# VGA.net
KiCad netlist of a schematic drawn in Altium Designer
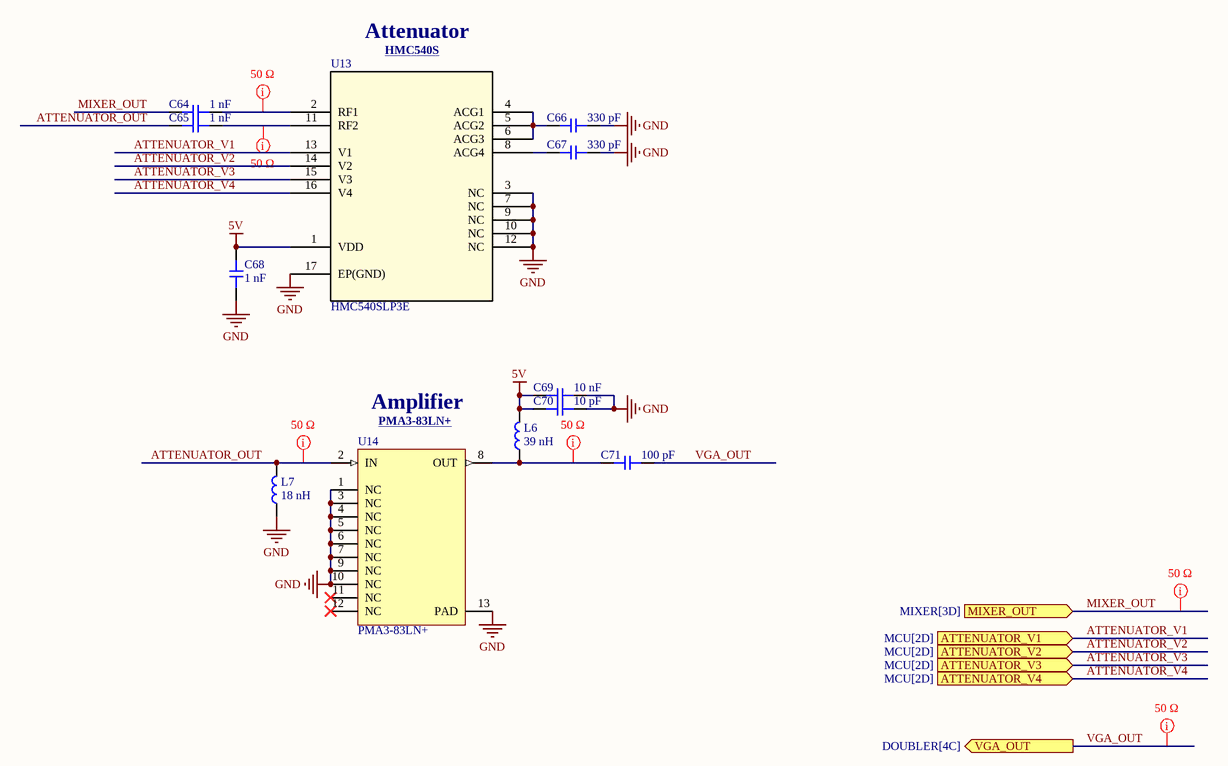
[diagram p0: VGA.SchDoc]

(export (version "E")
  (design (tool "Eeschema 10.0.6"))
  (components
    (comp (ref "C64")
      (value "1 nF")
      (footprint "CAP_0402")
      (description "50V 1nF X7R ±10% 0402 Multilayer Ceramic Capacitors MLCC - SMD/SMT ROHS")
      (fields
        (field (name "MANUFACTURER") "Yageo")
        (field (name "MANUFACTURER PART NUMBER") "CC0402KRX7R9BB102")
      )
      (libsource (lib "Titan") (part "CAP"))
    )
    (comp (ref "C65")
      (value "1 nF")
      (footprint "CAP_0402")
      (description "50V 1nF X7R ±10% 0402 Multilayer Ceramic Capacitors MLCC - SMD/SMT ROHS")
      (fields
        (field (name "MANUFACTURER") "Yageo")
        (field (name "MANUFACTURER PART NUMBER") "CC0402KRX7R9BB102")
      )
      (libsource (lib "Titan") (part "CAP"))
    )
    (comp (ref "C66")
      (value "330 pF")
      (footprint "CAP_0402")
      (description "50V 330pF C0G ±5% 0402 Multilayer Ceramic Capacitors MLCC - SMD/SMT ROHS")
      (fields
        (field (name "MANUFACTURER") "Murata Electronics")
        (field (name "MANUFACTURER PART NUMBER") "GRM1555C1H331JA01D")
      )
      (libsource (lib "Titan") (part "CAP"))
    )
    (comp (ref "C67")
      (value "330 pF")
      (footprint "CAP_0402")
      (description "50V 330pF C0G ±5% 0402 Multilayer Ceramic Capacitors MLCC - SMD/SMT ROHS")
      (fields
        (field (name "MANUFACTURER") "Murata Electronics")
        (field (name "MANUFACTURER PART NUMBER") "GRM1555C1H331JA01D")
      )
      (libsource (lib "Titan") (part "CAP"))
    )
    (comp (ref "C68")
      (value "1 nF")
      (footprint "CAP_0402")
      (description "50V 1nF X7R ±10% 0402 Multilayer Ceramic Capacitors MLCC - SMD/SMT ROHS")
      (fields
        (field (name "MANUFACTURER") "Yageo")
        (field (name "MANUFACTURER PART NUMBER") "CC0402KRX7R9BB102")
      )
      (libsource (lib "Titan") (part "CAP"))
    )
    (comp (ref "C69")
      (value "10 nF")
      (footprint "CAP_0402")
      (description "Multilayer Ceramic Capacitor, 0.01 uF, 25 V, ± 10%, X7R, 0402 [1005 Metric]")
      (fields
        (field (name "MANUFACTURER") "Murata Electronics")
        (field (name "MANUFACTURER PART NUMBER") "GRM155R71E103KA01D")
      )
      (libsource (lib "Titan") (part "CAP"))
    )
    (comp (ref "C70")
      (value "10 pF")
      (footprint "CAP_0402")
      (description "50V 10pF C0G ±1% 0402 Multilayer Ceramic Capacitors MLCC - SMD/SMT ROHS")
      (fields
        (field (name "MANUFACTURER") "Murata Electronics")
        (field (name "MANUFACTURER PART NUMBER") "GRM1555C1H100FA01D")
      )
      (libsource (lib "Titan") (part "CAP"))
    )
    (comp (ref "C71")
      (value "100 pF")
      (footprint "CAP_0402")
      (description "50V 100pF NP0 ±5% 0402 Multilayer Ceramic Capacitors MLCC - SMD/SMT ROHS")
      (fields
        (field (name "MANUFACTURER") "Yageo")
        (field (name "MANUFACTURER PART NUMBER") "CC0402JRNPO9BN101")
      )
      (libsource (lib "Titan") (part "CAP"))
    )
    (comp (ref "L6")
      (value "39 nH")
      (footprint "IND_0402")
      (description "Inductor RF Wirewound 0.039uH 5% 250MHz 25Q-Factor Ceramic 0.32A 0.55Ohm DCR 0402 T/R")
      (fields
        (field (name "MANUFACTURER") "Bourns Inc.")
        (field (name "MANUFACTURER PART NUMBER") "CW100505-39NJ")
      )
      (libsource (lib "Titan") (part "IND"))
    )
    (comp (ref "L7")
      (value "18 nH")
      (footprint "IND_0402")
      (description "Inductor RF Chip Multi-Layer 18nH 5% 100MHz 8Q-Factor Air 300mA 360mOhm DCR 0402 Paper T/R")
      (fields
        (field (name "MANUFACTURER") "Murata Electronics")
        (field (name "MANUFACTURER PART NUMBER") "LQG15HS18NJ02D")
      )
      (libsource (lib "Titan") (part "IND"))
    )
    (comp (ref "U13")
      (value "HMC540SLP3E")
      (footprint "HCP_16_1_ADI")
      (description "RF ATTENUATOR 15DB 16VFQFN RF Attenuators 15dB 100 MHz ~ 8 GHz 16-VFQFN Exposed Pad")
      (fields
        (field (name "MANUFACTURER") "Analog Devices")
        (field (name "COPYRIGHT") "Copyright (C) 2026 Ultra Librarian. All rights reserved.")
      )
      (libsource (lib "HMC540SLP3E") (part "HMC540SLP3E"))
    )
    (comp (ref "U14")
      (value "PMA3-83LN+")
      (footprint "PL-456")
      (description "1.3dB 0.5GHz~8GHz 21.3dB , LTE, SATCOM, UMTS, WiFi, WiMAX, WLAN QFN-12-EP(3x3) RF Amplifiers ROHS")
      (fields (field (name "MANUFACTURER") "Mini-Circuits"))
      (libsource (lib "Titan") (part "PMA3-83LN+"))
    )
  )
  (nets
    (net (code "1") (name "/ATTENUATOR_OUT") (class "Default")
      (node (ref "C65") (pin "2") (pintype "passive"))
      (node (ref "L7") (pin "2") (pintype "passive"))
      (node (ref "U14") (pin "2") (pinfunction "IN_2") (pintype "input"))
    )
    (net (code "2") (name "/ATTENUATOR_V1") (class "Default")
      (node (ref "U13") (pin "13") (pinfunction "V1_13") (pintype "passive"))
    )
    (net (code "3") (name "/ATTENUATOR_V2") (class "Default")
      (node (ref "U13") (pin "14") (pinfunction "V2_14") (pintype "passive"))
    )
    (net (code "4") (name "/ATTENUATOR_V3") (class "Default")
      (node (ref "U13") (pin "15") (pinfunction "V3_15") (pintype "passive"))
    )
    (net (code "5") (name "/ATTENUATOR_V4") (class "Default")
      (node (ref "U13") (pin "16") (pinfunction "V4_16") (pintype "passive"))
    )
    (net (code "6") (name "/MIXER_OUT") (class "Default") (node (ref "C64") (pin "2") (pintype "passive")))
    (net (code "7") (name "/VGA_OUT") (class "Default") (node (ref "C71") (pin "1") (pintype "passive")))
    (net (code "8") (name "5V") (class "Default")
      (node (ref "C68") (pin "2") (pintype "passive"))
      (node (ref "C69") (pin "1") (pintype "passive"))
      (node (ref "C70") (pin "1") (pintype "passive"))
      (node (ref "L6") (pin "2") (pintype "passive"))
      (node (ref "U13") (pin "1") (pinfunction "VDD_1") (pintype "passive"))
    )
    (net (code "9") (name "GND") (class "Default")
      (node (ref "C66") (pin "2") (pintype "passive"))
      (node (ref "C67") (pin "2") (pintype "passive"))
      (node (ref "C68") (pin "1") (pintype "passive"))
      (node (ref "C69") (pin "2") (pintype "passive"))
      (node (ref "C70") (pin "2") (pintype "passive"))
      (node (ref "L7") (pin "1") (pintype "passive"))
      (node (ref "U13") (pin "10") (pinfunction "NC_10") (pintype "passive"))
      (node (ref "U13") (pin "12") (pinfunction "NC_12") (pintype "passive"))
      (node (ref "U13") (pin "17") (pinfunction "EP(GND)_17") (pintype "passive"))
      (node (ref "U13") (pin "3") (pinfunction "NC_3") (pintype "passive"))
      (node (ref "U13") (pin "7") (pinfunction "NC_7") (pintype "passive"))
      (node (ref "U13") (pin "9") (pinfunction "NC_9") (pintype "passive"))
      (node (ref "U14") (pin "1") (pinfunction "NC_1") (pintype "passive"))
      (node (ref "U14") (pin "10") (pinfunction "NC_10") (pintype "passive"))
      (node (ref "U14") (pin "13") (pinfunction "PAD_13") (pintype "passive"))
      (node (ref "U14") (pin "3") (pinfunction "NC_3") (pintype "passive"))
      (node (ref "U14") (pin "4") (pinfunction "NC_4") (pintype "passive"))
      (node (ref "U14") (pin "5") (pinfunction "NC_5") (pintype "passive"))
      (node (ref "U14") (pin "6") (pinfunction "NC_6") (pintype "passive"))
      (node (ref "U14") (pin "7") (pinfunction "NC_7") (pintype "passive"))
      (node (ref "U14") (pin "9") (pinfunction "NC_9") (pintype "passive"))
    )
    (net (code "10") (name "Net-(U13-ACG1)") (class "Default")
      (node (ref "C66") (pin "1") (pintype "passive"))
      (node (ref "U13") (pin "4") (pinfunction "ACG1_4") (pintype "passive"))
      (node (ref "U13") (pin "5") (pinfunction "ACG2_5") (pintype "passive"))
      (node (ref "U13") (pin "6") (pinfunction "ACG3_6") (pintype "passive"))
    )
    (net (code "11") (name "Net-(U13-ACG4)") (class "Default")
      (node (ref "C67") (pin "1") (pintype "passive"))
      (node (ref "U13") (pin "8") (pinfunction "ACG4_8") (pintype "passive"))
    )
    (net (code "12") (name "Net-(U13-RF1)") (class "Default")
      (node (ref "C64") (pin "1") (pintype "passive"))
      (node (ref "U13") (pin "2") (pinfunction "RF1_2") (pintype "passive"))
    )
    (net (code "13") (name "Net-(U13-RF2)") (class "Default")
      (node (ref "C65") (pin "1") (pintype "passive"))
      (node (ref "U13") (pin "11") (pinfunction "RF2_11") (pintype "passive"))
    )
    (net (code "14") (name "Net-(U14-OUT)") (class "Default")
      (node (ref "C71") (pin "2") (pintype "passive"))
      (node (ref "L6") (pin "1") (pintype "passive"))
      (node (ref "U14") (pin "8") (pinfunction "OUT_8") (pintype "output"))
    )
    (net (code "15") (name "unconnected-(U14-NC-Pad11)") (class "Default")
      (node (ref "U14") (pin "11") (pinfunction "NC_11") (pintype "passive+no_connect"))
    )
    (net (code "16") (name "unconnected-(U14-NC-Pad12)") (class "Default")
      (node (ref "U14") (pin "12") (pinfunction "NC_12") (pintype "passive+no_connect"))
    )
  )
)
